# Onboard_IO.net
KiCad netlist of a schematic drawn in Altium Designer
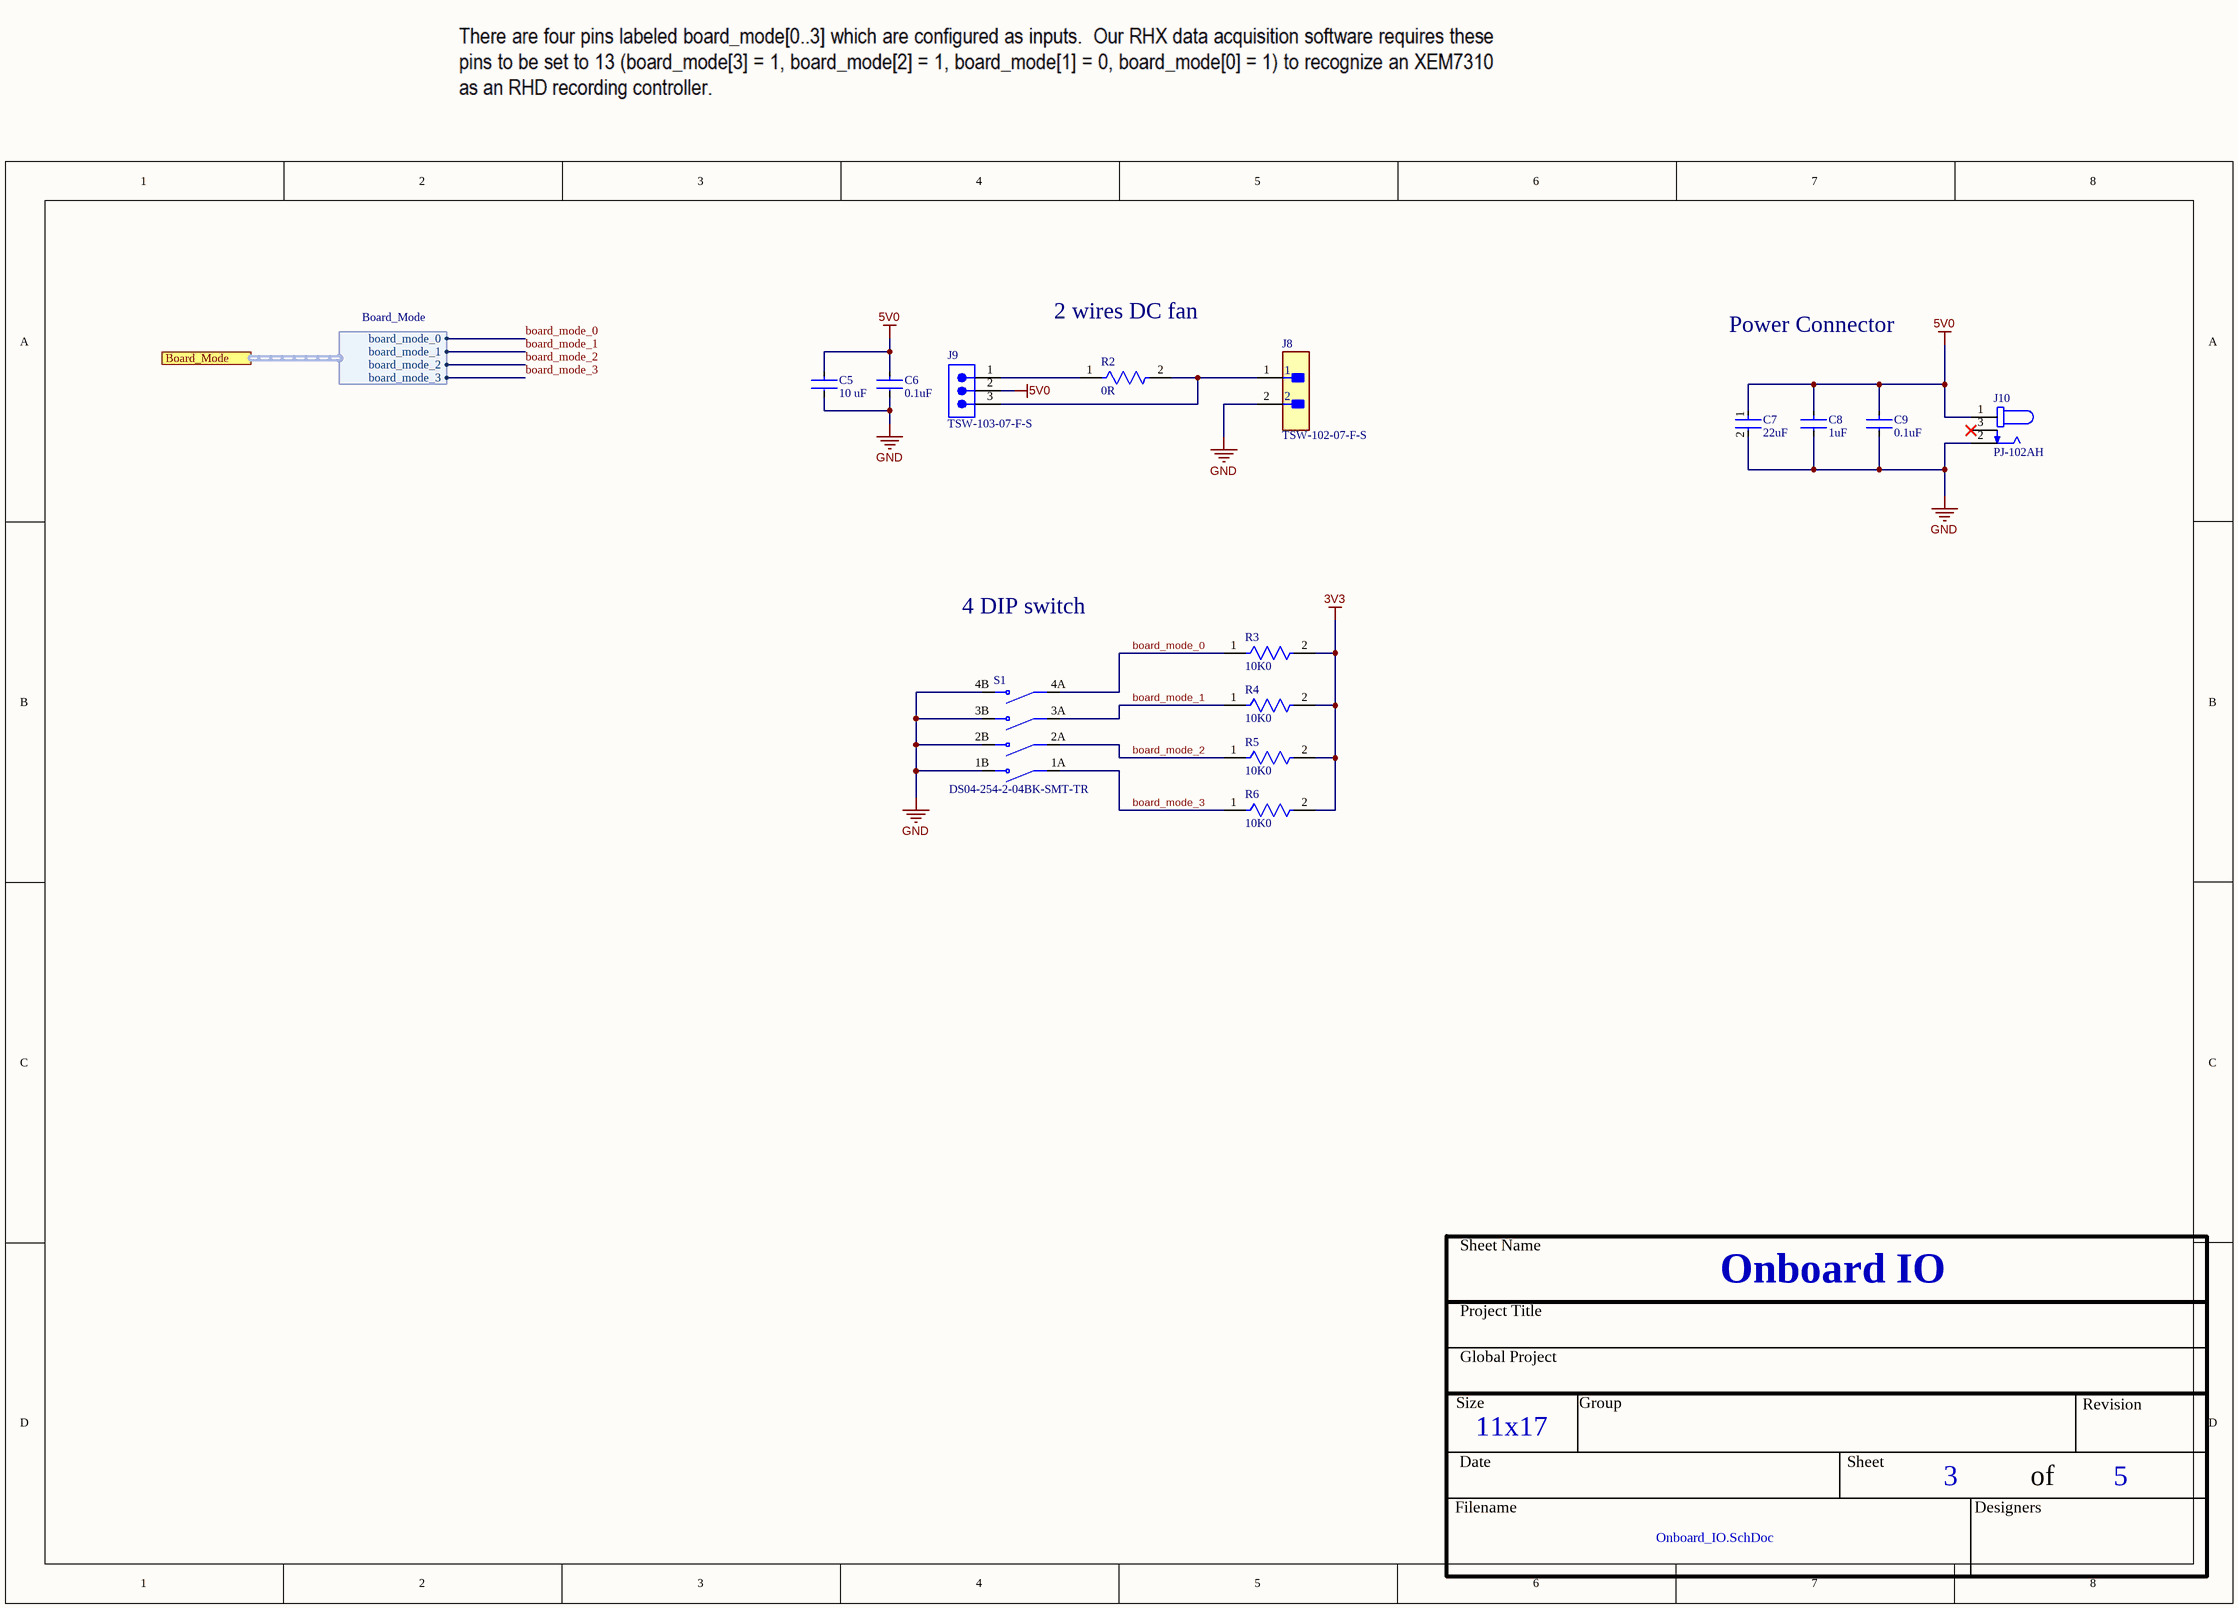
[diagram p0: Onboard_IO.SchDoc]

(export (version "E")
  (design (tool "Eeschema 10.0.6"))
  (components
    (comp (ref "C5")
      (value "10 uF")
      (footprint "FP-GRM188-0_2-IPC_C")
      (description "Chip Multilayer Ceramic Capacitors for General Purpose, 0603, 10uF, X7R, 15%, 10%, 10V")
      (libsource (lib "Capacitors") (part "CAP_10U0_0603"))
    )
    (comp (ref "C6")
      (value "0.1uF")
      (footprint "FP-CC0603-DA-IPC_B")
      (description "CAP CER 0.1UF 50V X7R 0603")
      (fields (field (name "MANUFACTURER") "YAGEO") (field (name "VOLTAGE") "50 V"))
      (libsource (lib "Capacitors") (part "CAP_0U10_0603"))
    )
    (comp (ref "C7")
      (value "22uF")
      (footprint "FP-GRM21B-0_2-e0_2_0_7-IPC_A")
      (description "Chip Multilayer Ceramic Capacitors for General Purpose, 0805, 22uF, X6S, 22%, 20%, 16V")
      (fields (field (name "TOLERANCE") "20%"))
      (libsource (lib "Capacitors") (part "CAP_22U0_0805"))
    )
    (comp (ref "C8")
      (value "1uF")
      (footprint "FP-CC0603-DA-IPC_B")
      (description "CAP CER 1UF 16V X7R 0603")
      (fields (field (name "TOLERANCE") "0.1") (field (name "MANUFACTURER") "YAGEO"))
      (libsource (lib "Capacitors") (part "CAP_1U00_0603"))
    )
    (comp (ref "C9")
      (value "0.1uF")
      (footprint "FP-CC0603-DA-IPC_B")
      (description "CAP CER 0.1UF 50V X7R 0603")
      (fields (field (name "MANUFACTURER") "YAGEO") (field (name "VOLTAGE") "50 V"))
      (libsource (lib "Capacitors") (part "CAP_0U10_0603"))
    )
    (comp (ref "J8")
      (value "TSW-102-07-F-S")
      (footprint "FP-TSW-102-07-F-S-MFG")
      (description "Connector Header Through Hole 2 position 0.100\" (2.54mm)")
      (libsource (lib "Connectors") (part "CON_HEADM_1X2"))
    )
    (comp (ref "J9")
      (value "TSW-103-07-F-S")
      (footprint "SMTC-TSW-103-07-X-S")
      (description "0.025\" SQ Post Header, Through-hole, Vertical, -55 to 125 degC, 2.54 mm Pitch, 3-Pin, Male, RoHS")
      (fields (field (name "MANUFACTURER") "Samtec"))
      (libsource (lib "Connectors") (part "CON_HEADM_1X3"))
    )
    (comp (ref "J10")
      (value "PJ-102AH")
      (footprint "CUI_PJ-102AH")
      (description "Power Barrel Connector Jack 2.00mm ID (0.079\"), 5.50mm OD (0.217\") Through Hole, Right Angle")
      (fields (field (name "MF") "Same Sky"))
      (libsource (lib "Connectors") (part "CON_PWR_24V_5A"))
    )
    (comp (ref "R2")
      (value "0R")
      (footprint "FP-RC0603-MFG")
      (description "RES SMD 0 OHM JUMPER 1/10W 0603")
      (fields
        (field (name "TOLERANCE") "1%")
        (field (name "OCTOPART") "https://octopart.com/rc0603fr-070rl-yageo-1180803")
      )
      (libsource (lib "Resistors") (part "RES_0R00_0603"))
    )
    (comp (ref "R3")
      (value "10K0")
      (footprint "FP-RC0603-0_55-IPC_B")
      (description "RES 10K OHM 1% 1/10W 0603")
      (fields (field (name "TOLERANCE") "1%"))
      (libsource (lib "Resistors") (part "RES_10K0_0603"))
    )
    (comp (ref "R4")
      (value "10K0")
      (footprint "FP-RC0603-0_55-IPC_B")
      (description "RES 10K OHM 1% 1/10W 0603")
      (fields (field (name "TOLERANCE") "1%"))
      (libsource (lib "Resistors") (part "RES_10K0_0603"))
    )
    (comp (ref "R5")
      (value "10K0")
      (footprint "FP-RC0603-0_55-IPC_B")
      (description "RES 10K OHM 1% 1/10W 0603")
      (fields (field (name "TOLERANCE") "1%"))
      (libsource (lib "Resistors") (part "RES_10K0_0603"))
    )
    (comp (ref "R6")
      (value "10K0")
      (footprint "FP-RC0603-0_55-IPC_B")
      (description "RES 10K OHM 1% 1/10W 0603")
      (fields (field (name "TOLERANCE") "1%"))
      (libsource (lib "Resistors") (part "RES_10K0_0603"))
    )
    (comp (ref "S1")
      (value "DS04-254-2-04BK-SMT-TR")
      (footprint "SW_DS04-254-2-04BK-SMT-TR")
      (description "Dip Switch SPST 4 Position Surface Mount Slide (Standard) Actuator 25mA 24VDC")
      (fields (field (name "MF") "Same Sky"))
      (libsource (lib "Miscellaneous") (part "SW_DIP_4_SMT"))
    )
  )
  (nets
    (net (code "2") (name "/board_mode_0") (class "Default")
      (node (ref "R3") (pin "1") (pinfunction "1_1") (pintype "passive"))
      (node (ref "S1") (pin "4A") (pinfunction "COM4_4A") (pintype "passive"))
    )
    (net (code "3") (name "/board_mode_1") (class "Default")
      (node (ref "R4") (pin "1") (pinfunction "1_1") (pintype "passive"))
      (node (ref "S1") (pin "3A") (pinfunction "COM3_3A") (pintype "passive"))
    )
    (net (code "4") (name "/board_mode_2") (class "Default")
      (node (ref "R5") (pin "1") (pinfunction "1_1") (pintype "passive"))
      (node (ref "S1") (pin "2A") (pinfunction "COM2_2A") (pintype "passive"))
    )
    (net (code "5") (name "/board_mode_3") (class "Default")
      (node (ref "R6") (pin "1") (pinfunction "1_1") (pintype "passive"))
      (node (ref "S1") (pin "1A") (pinfunction "COM1_1A") (pintype "passive"))
    )
    (net (code "7") (name "3V3") (class "Default")
      (node (ref "R3") (pin "2") (pinfunction "2_2") (pintype "passive"))
      (node (ref "R4") (pin "2") (pinfunction "2_2") (pintype "passive"))
      (node (ref "R5") (pin "2") (pinfunction "2_2") (pintype "passive"))
      (node (ref "R6") (pin "2") (pinfunction "2_2") (pintype "passive"))
    )
    (net (code "8") (name "5V0") (class "Default")
      (node (ref "C5") (pin "1") (pinfunction "1_1") (pintype "passive"))
      (node (ref "C6") (pin "1") (pinfunction "1_1") (pintype "passive"))
      (node (ref "C7") (pin "1") (pinfunction "1_1") (pintype "passive"))
      (node (ref "C8") (pin "1") (pinfunction "1_1") (pintype "passive"))
      (node (ref "C9") (pin "1") (pinfunction "1_1") (pintype "passive"))
      (node (ref "J10") (pin "1") (pinfunction "1_1") (pintype "passive"))
      (node (ref "J9") (pin "2") (pinfunction "2_2") (pintype "passive"))
    )
    (net (code "9") (name "GND") (class "Default")
      (node (ref "C5") (pin "2") (pinfunction "2_2") (pintype "passive"))
      (node (ref "C6") (pin "2") (pinfunction "2_2") (pintype "passive"))
      (node (ref "C7") (pin "2") (pinfunction "2_2") (pintype "passive"))
      (node (ref "C8") (pin "2") (pinfunction "2_2") (pintype "passive"))
      (node (ref "C9") (pin "2") (pinfunction "2_2") (pintype "passive"))
      (node (ref "J10") (pin "2") (pinfunction "2_2") (pintype "passive"))
      (node (ref "J8") (pin "2") (pinfunction "2_2") (pintype "passive"))
      (node (ref "S1") (pin "1B") (pinfunction "NO1_1B") (pintype "passive"))
      (node (ref "S1") (pin "2B") (pinfunction "NO2_2B") (pintype "passive"))
      (node (ref "S1") (pin "3B") (pinfunction "NO3_3B") (pintype "passive"))
      (node (ref "S1") (pin "4B") (pinfunction "NO4_4B") (pintype "passive"))
    )
    (net (code "10") (name "Net-(J8-Pad1)") (class "Default")
      (node (ref "J8") (pin "1") (pinfunction "1_1") (pintype "passive"))
      (node (ref "J9") (pin "3") (pinfunction "3_3") (pintype "passive"))
      (node (ref "R2") (pin "2") (pinfunction "2_2") (pintype "passive"))
    )
    (net (code "11") (name "Net-(J9-Pad1)") (class "Default")
      (node (ref "J9") (pin "1") (pinfunction "1_1") (pintype "passive"))
      (node (ref "R2") (pin "1") (pinfunction "1_1") (pintype "passive"))
    )
    (net (code "12") (name "unconnected-(J10-Pad3)") (class "Default")
      (node (ref "J10") (pin "3") (pinfunction "3_3") (pintype "passive+no_connect"))
    )
  )
)
